# MouseBox_PortBreakout_SMT_r1.net
KiCad netlist of a schematic drawn in EAGLE
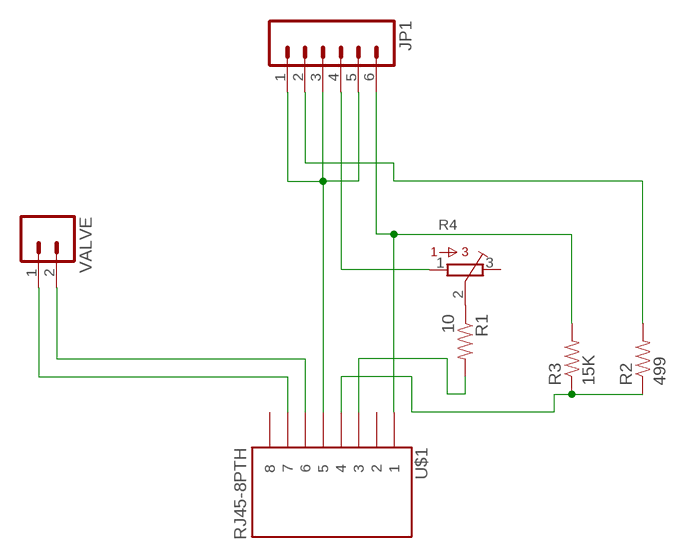
[diagram p0: schematic, sheet 1]

(export (version "E")
  (design (tool "Eeschema 10.0.6"))
  (components
    (comp (ref "JP1")
      (value "M063.5MM-6")
      (footprint "eagle-import:SCREWTERMINAL-3.5MM-6")
      (libsource (lib "eagle-import") (part "M063.5MM-6"))
    )
    (comp (ref "R1")
      (value "10")
      (footprint "eagle-import:1206")
      (libsource (lib "eagle-import") (part "RESISTOR1206"))
    )
    (comp (ref "R2")
      (value "499")
      (footprint "eagle-import:1206")
      (libsource (lib "eagle-import") (part "RESISTOR1206"))
    )
    (comp (ref "R3")
      (value "15K")
      (footprint "eagle-import:1206")
      (libsource (lib "eagle-import") (part "RESISTOR1206"))
    )
    (comp (ref "R4")
      (value "3362R")
      (footprint "eagle-import:3362R")
      (libsource (lib "eagle-import") (part "3362R"))
    )
    (comp (ref "U$1")
      (value "RJ45-8PTH")
      (footprint "eagle-import:RJ45-8")
      (libsource (lib "eagle-import") (part "RJ45-8PTH"))
    )
    (comp (ref "VALVE")
      (value "M023.5MM_LOCK")
      (footprint "eagle-import:SCREWTERMINAL-3.5MM-2_LOCK")
      (libsource (lib "eagle-import") (part "M023.5MM_LOCK"))
    )
  )
  (nets
    (net (code "1") (name "Net-(JP1-Pad1)") (class "Default")
      (node (ref "JP1") (pin "1") (pinfunction "1_1") (pintype "passive"))
      (node (ref "JP1") (pin "3") (pinfunction "3_3") (pintype "passive"))
      (node (ref "JP1") (pin "5") (pinfunction "5_5") (pintype "passive"))
      (node (ref "U$1") (pin "5") (pinfunction "5_5") (pintype "bidirectional"))
    )
    (net (code "2") (name "Net-(JP1-Pad2)") (class "Default")
      (node (ref "JP1") (pin "2") (pinfunction "2_2") (pintype "passive"))
      (node (ref "R2") (pin "2") (pinfunction "2_2") (pintype "passive"))
    )
    (net (code "3") (name "Net-(JP1-Pad4)") (class "Default")
      (node (ref "JP1") (pin "4") (pinfunction "4_4") (pintype "passive"))
      (node (ref "R4") (pin "1") (pinfunction "1_1") (pintype "passive"))
    )
    (net (code "4") (name "Net-(JP1-Pad6)") (class "Default")
      (node (ref "JP1") (pin "6") (pinfunction "6_6") (pintype "passive"))
      (node (ref "R3") (pin "2") (pinfunction "2_2") (pintype "passive"))
      (node (ref "U$1") (pin "1") (pinfunction "1_1") (pintype "bidirectional"))
    )
    (net (code "5") (name "Net-(R1-Pad1)") (class "Default")
      (node (ref "R1") (pin "1") (pinfunction "1_1") (pintype "passive"))
      (node (ref "R4") (pin "2") (pinfunction "2_2") (pintype "passive"))
    )
    (net (code "6") (name "Net-(R1-Pad2)") (class "Default")
      (node (ref "R1") (pin "2") (pinfunction "2_2") (pintype "passive"))
      (node (ref "U$1") (pin "3") (pinfunction "3_3") (pintype "bidirectional"))
    )
    (net (code "7") (name "Net-(R2-Pad1)") (class "Default")
      (node (ref "R2") (pin "1") (pinfunction "1_1") (pintype "passive"))
      (node (ref "R3") (pin "1") (pinfunction "1_1") (pintype "passive"))
      (node (ref "U$1") (pin "4") (pinfunction "4_4") (pintype "bidirectional"))
    )
    (net (code "8") (name "Net-(U$1-Pad6)") (class "Default")
      (node (ref "U$1") (pin "6") (pinfunction "6_6") (pintype "bidirectional"))
      (node (ref "VALVE") (pin "2") (pinfunction "2_2") (pintype "passive"))
    )
    (net (code "9") (name "Net-(U$1-Pad7)") (class "Default")
      (node (ref "U$1") (pin "7") (pinfunction "7_7") (pintype "bidirectional"))
      (node (ref "VALVE") (pin "1") (pinfunction "1_1") (pintype "passive"))
    )
    (net (code "10") (name "unconnected-(R4-Pad3)") (class "Default")
      (node (ref "R4") (pin "3") (pinfunction "3_3") (pintype "passive"))
    )
    (net (code "11") (name "unconnected-(U$1-Pad2)") (class "Default")
      (node (ref "U$1") (pin "2") (pinfunction "2_2") (pintype "bidirectional"))
    )
    (net (code "12") (name "unconnected-(U$1-Pad8)") (class "Default")
      (node (ref "U$1") (pin "8") (pinfunction "8_8") (pintype "bidirectional"))
    )
  )
)
